# 8But.net
KiCad netlist of a schematic drawn in EAGLE
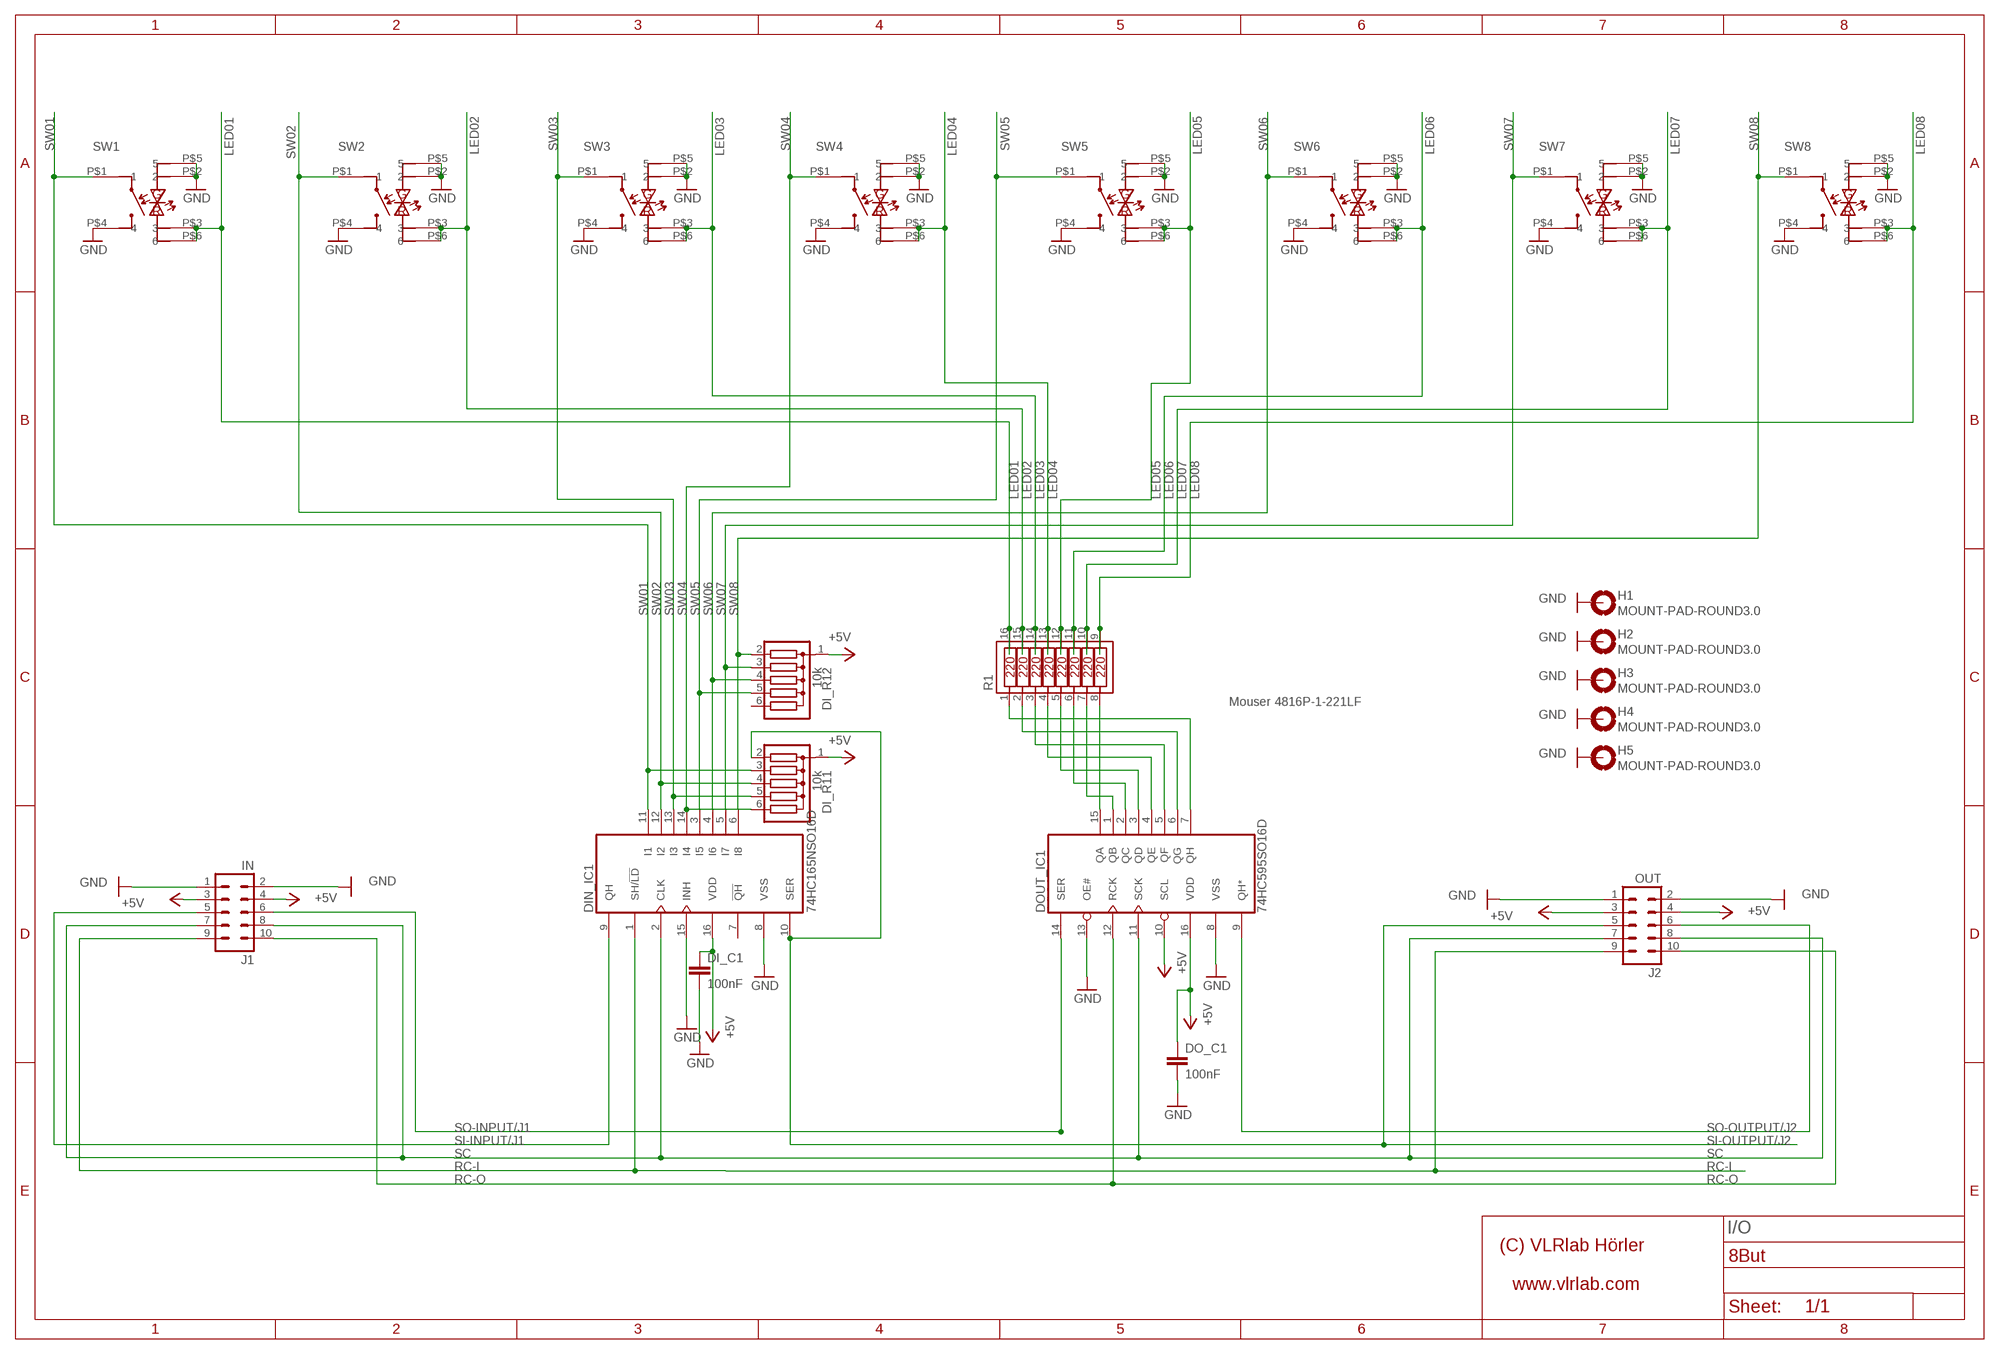
[diagram p0: schematic, sheet 1]

(export (version "E")
  (design (tool "Eeschema 10.0.6"))
  (components
    (comp (ref "DIN_IC1")
      (value "74HC165NSO16D")
      (footprint "eagle-import:SO16D")
      (libsource (lib "eagle-import") (part "74HC165NSO16D"))
    )
    (comp (ref "DI_C1")
      (value "100nF")
      (footprint "eagle-import:C5B3")
      (libsource (lib "eagle-import") (part "C5/3"))
    )
    (comp (ref "DI_R11")
      (value "10k")
      (footprint "eagle-import:SIL6")
      (libsource (lib "eagle-import") (part "4306R"))
    )
    (comp (ref "DI_R12")
      (value "10k")
      (footprint "eagle-import:SIL6")
      (libsource (lib "eagle-import") (part "4306R"))
    )
    (comp (ref "DOUT_IC1")
      (value "74HC595SO16D")
      (footprint "eagle-import:SO16D")
      (libsource (lib "eagle-import") (part "595-541-165-uln2803_74HC595SO16D"))
    )
    (comp (ref "DO_C1")
      (value "100nF")
      (footprint "eagle-import:C5B3")
      (libsource (lib "eagle-import") (part "C5/3"))
    )
    (comp (ref "H1")
      (value "MOUNT-PAD-ROUND3.0")
      (footprint "eagle-import:3,0-PAD")
      (libsource (lib "eagle-import") (part "MOUNT-PAD-ROUND3.0"))
    )
    (comp (ref "H2")
      (value "MOUNT-PAD-ROUND3.0")
      (footprint "eagle-import:3,0-PAD")
      (libsource (lib "eagle-import") (part "MOUNT-PAD-ROUND3.0"))
    )
    (comp (ref "H3")
      (value "MOUNT-PAD-ROUND3.0")
      (footprint "eagle-import:3,0-PAD")
      (libsource (lib "eagle-import") (part "MOUNT-PAD-ROUND3.0"))
    )
    (comp (ref "H4")
      (value "MOUNT-PAD-ROUND3.0")
      (footprint "eagle-import:3,0-PAD")
      (libsource (lib "eagle-import") (part "MOUNT-PAD-ROUND3.0"))
    )
    (comp (ref "H5")
      (value "MOUNT-PAD-ROUND3.0")
      (footprint "eagle-import:3,0-PAD")
      (libsource (lib "eagle-import") (part "MOUNT-PAD-ROUND3.0"))
    )
    (comp (ref "J1")
      (value "IN")
      (footprint "eagle-import:ML10")
      (libsource (lib "eagle-import") (part "ML10"))
    )
    (comp (ref "J2")
      (value "OUT")
      (footprint "eagle-import:ML10")
      (libsource (lib "eagle-import") (part "ML10"))
    )
    (comp (ref "R1")
      (value "4816P-1SOIC16W")
      (footprint "eagle-import:SOIC16W")
      (libsource (lib "eagle-import") (part "4816P-1SOIC16W"))
    )
    (comp (ref "SW1")
      (value "COMB_G3+G5")
      (footprint "eagle-import:COMB_G3+G5")
      (libsource (lib "eagle-import") (part "COMB_G3+G5"))
    )
    (comp (ref "SW2")
      (value "COMB_G3+G5")
      (footprint "eagle-import:COMB_G3+G5")
      (libsource (lib "eagle-import") (part "COMB_G3+G5"))
    )
    (comp (ref "SW3")
      (value "COMB_G3+G5")
      (footprint "eagle-import:COMB_G3+G5")
      (libsource (lib "eagle-import") (part "COMB_G3+G5"))
    )
    (comp (ref "SW4")
      (value "COMB_G3+G5")
      (footprint "eagle-import:COMB_G3+G5")
      (libsource (lib "eagle-import") (part "COMB_G3+G5"))
    )
    (comp (ref "SW5")
      (value "COMB_G3+G5")
      (footprint "eagle-import:COMB_G3+G5")
      (libsource (lib "eagle-import") (part "COMB_G3+G5"))
    )
    (comp (ref "SW6")
      (value "COMB_G3+G5")
      (footprint "eagle-import:COMB_G3+G5")
      (libsource (lib "eagle-import") (part "COMB_G3+G5"))
    )
    (comp (ref "SW7")
      (value "COMB_G3+G5")
      (footprint "eagle-import:COMB_G3+G5")
      (libsource (lib "eagle-import") (part "COMB_G3+G5"))
    )
    (comp (ref "SW8")
      (value "COMB_G3+G5")
      (footprint "eagle-import:COMB_G3+G5")
      (libsource (lib "eagle-import") (part "COMB_G3+G5"))
    )
  )
  (nets
    (net (code "1") (name "+5V") (class "Default")
      (node (ref "DIN_IC1") (pin "16") (pinfunction "VDD_16") (pintype "power_in"))
      (node (ref "DI_C1") (pin "1") (pinfunction "1_1") (pintype "passive"))
      (node (ref "DI_R11") (pin "1") (pinfunction "1_1") (pintype "passive"))
      (node (ref "DI_R12") (pin "1") (pinfunction "1_1") (pintype "passive"))
      (node (ref "DOUT_IC1") (pin "10") (pinfunction "SCL_10") (pintype "input"))
      (node (ref "DOUT_IC1") (pin "16") (pinfunction "VDD_16") (pintype "power_in"))
      (node (ref "DO_C1") (pin "1") (pinfunction "1_1") (pintype "passive"))
      (node (ref "J1") (pin "3") (pinfunction "3_3") (pintype "passive"))
      (node (ref "J1") (pin "4") (pinfunction "4_4") (pintype "passive"))
      (node (ref "J2") (pin "3") (pinfunction "3_3") (pintype "passive"))
      (node (ref "J2") (pin "4") (pinfunction "4_4") (pintype "passive"))
    )
    (net (code "2") (name "/LED01") (class "Default")
      (node (ref "R1") (pin "16") (pinfunction "P$16_16") (pintype "passive"))
      (node (ref "SW1") (pin "P$3") (pinfunction "3_P$3") (pintype "bidirectional"))
      (node (ref "SW1") (pin "P$6") (pinfunction "6_P$6") (pintype "bidirectional"))
    )
    (net (code "3") (name "/LED02") (class "Default")
      (node (ref "R1") (pin "15") (pinfunction "P$15_15") (pintype "passive"))
      (node (ref "SW2") (pin "P$3") (pinfunction "3_P$3") (pintype "bidirectional"))
      (node (ref "SW2") (pin "P$6") (pinfunction "6_P$6") (pintype "bidirectional"))
    )
    (net (code "4") (name "/LED03") (class "Default")
      (node (ref "R1") (pin "14") (pinfunction "P$14_14") (pintype "passive"))
      (node (ref "SW3") (pin "P$3") (pinfunction "3_P$3") (pintype "bidirectional"))
      (node (ref "SW3") (pin "P$6") (pinfunction "6_P$6") (pintype "bidirectional"))
    )
    (net (code "5") (name "/LED04") (class "Default")
      (node (ref "R1") (pin "13") (pinfunction "P$13_13") (pintype "passive"))
      (node (ref "SW4") (pin "P$3") (pinfunction "3_P$3") (pintype "bidirectional"))
      (node (ref "SW4") (pin "P$6") (pinfunction "6_P$6") (pintype "bidirectional"))
    )
    (net (code "6") (name "/LED05") (class "Default")
      (node (ref "R1") (pin "12") (pinfunction "P$12_12") (pintype "passive"))
      (node (ref "SW5") (pin "P$3") (pinfunction "3_P$3") (pintype "bidirectional"))
      (node (ref "SW5") (pin "P$6") (pinfunction "6_P$6") (pintype "bidirectional"))
    )
    (net (code "7") (name "/LED06") (class "Default")
      (node (ref "R1") (pin "11") (pinfunction "P$11_11") (pintype "passive"))
      (node (ref "SW6") (pin "P$3") (pinfunction "3_P$3") (pintype "bidirectional"))
      (node (ref "SW6") (pin "P$6") (pinfunction "6_P$6") (pintype "bidirectional"))
    )
    (net (code "8") (name "/LED07") (class "Default")
      (node (ref "R1") (pin "10") (pinfunction "P$10_10") (pintype "passive"))
      (node (ref "SW7") (pin "P$3") (pinfunction "3_P$3") (pintype "bidirectional"))
      (node (ref "SW7") (pin "P$6") (pinfunction "6_P$6") (pintype "bidirectional"))
    )
    (net (code "9") (name "/LED08") (class "Default")
      (node (ref "R1") (pin "9") (pinfunction "P$9_9") (pintype "passive"))
      (node (ref "SW8") (pin "P$3") (pinfunction "3_P$3") (pintype "bidirectional"))
      (node (ref "SW8") (pin "P$6") (pinfunction "6_P$6") (pintype "bidirectional"))
    )
    (net (code "10") (name "/RC-I") (class "Default")
      (node (ref "DIN_IC1") (pin "1") (pinfunction "SH/~{LD}_1") (pintype "input"))
      (node (ref "J1") (pin "9") (pinfunction "9_9") (pintype "passive"))
      (node (ref "J2") (pin "9") (pinfunction "9_9") (pintype "passive"))
    )
    (net (code "11") (name "/RC-O") (class "Default")
      (node (ref "DOUT_IC1") (pin "12") (pinfunction "RCK_12") (pintype "input"))
      (node (ref "J1") (pin "10") (pinfunction "10_10") (pintype "passive"))
      (node (ref "J2") (pin "10") (pinfunction "10_10") (pintype "passive"))
    )
    (net (code "12") (name "/SC") (class "Default")
      (node (ref "DIN_IC1") (pin "2") (pinfunction "CLK_2") (pintype "input"))
      (node (ref "DOUT_IC1") (pin "11") (pinfunction "SCK_11") (pintype "input"))
      (node (ref "J1") (pin "7") (pinfunction "7_7") (pintype "passive"))
      (node (ref "J1") (pin "8") (pinfunction "8_8") (pintype "passive"))
      (node (ref "J2") (pin "7") (pinfunction "7_7") (pintype "passive"))
      (node (ref "J2") (pin "8") (pinfunction "8_8") (pintype "passive"))
    )
    (net (code "13") (name "/SI-INPUT{slash}J1") (class "Default")
      (node (ref "DIN_IC1") (pin "9") (pinfunction "QH_9") (pintype "output"))
      (node (ref "J1") (pin "5") (pinfunction "5_5") (pintype "passive"))
    )
    (net (code "14") (name "/SI-OUTPUT{slash}J2") (class "Default")
      (node (ref "DIN_IC1") (pin "10") (pinfunction "SER_10") (pintype "input"))
      (node (ref "DI_R11") (pin "2") (pinfunction "2_2") (pintype "passive"))
      (node (ref "J2") (pin "5") (pinfunction "5_5") (pintype "passive"))
    )
    (net (code "15") (name "/SO-INPUT{slash}J1") (class "Default")
      (node (ref "DOUT_IC1") (pin "14") (pinfunction "SER_14") (pintype "input"))
      (node (ref "J1") (pin "6") (pinfunction "6_6") (pintype "passive"))
    )
    (net (code "16") (name "/SO-OUTPUT{slash}J2") (class "Default")
      (node (ref "DOUT_IC1") (pin "9") (pinfunction "QH*_9") (pintype "tri_state"))
      (node (ref "J2") (pin "6") (pinfunction "6_6") (pintype "passive"))
    )
    (net (code "17") (name "/SW01") (class "Default")
      (node (ref "DIN_IC1") (pin "11") (pinfunction "I1_11") (pintype "input"))
      (node (ref "DI_R11") (pin "3") (pinfunction "3_3") (pintype "passive"))
      (node (ref "SW1") (pin "P$1") (pinfunction "1_P$1") (pintype "bidirectional"))
    )
    (net (code "18") (name "/SW02") (class "Default")
      (node (ref "DIN_IC1") (pin "12") (pinfunction "I2_12") (pintype "input"))
      (node (ref "DI_R11") (pin "4") (pinfunction "4_4") (pintype "passive"))
      (node (ref "SW2") (pin "P$1") (pinfunction "1_P$1") (pintype "bidirectional"))
    )
    (net (code "19") (name "/SW03") (class "Default")
      (node (ref "DIN_IC1") (pin "13") (pinfunction "I3_13") (pintype "input"))
      (node (ref "DI_R11") (pin "5") (pinfunction "5_5") (pintype "passive"))
      (node (ref "SW3") (pin "P$1") (pinfunction "1_P$1") (pintype "bidirectional"))
    )
    (net (code "20") (name "/SW04") (class "Default")
      (node (ref "DIN_IC1") (pin "14") (pinfunction "I4_14") (pintype "input"))
      (node (ref "DI_R11") (pin "6") (pinfunction "6_6") (pintype "passive"))
      (node (ref "SW4") (pin "P$1") (pinfunction "1_P$1") (pintype "bidirectional"))
    )
    (net (code "21") (name "/SW05") (class "Default")
      (node (ref "DIN_IC1") (pin "3") (pinfunction "I5_3") (pintype "input"))
      (node (ref "DI_R12") (pin "5") (pinfunction "5_5") (pintype "passive"))
      (node (ref "SW5") (pin "P$1") (pinfunction "1_P$1") (pintype "bidirectional"))
    )
    (net (code "22") (name "/SW06") (class "Default")
      (node (ref "DIN_IC1") (pin "4") (pinfunction "I6_4") (pintype "input"))
      (node (ref "DI_R12") (pin "4") (pinfunction "4_4") (pintype "passive"))
      (node (ref "SW6") (pin "P$1") (pinfunction "1_P$1") (pintype "bidirectional"))
    )
    (net (code "23") (name "/SW07") (class "Default")
      (node (ref "DIN_IC1") (pin "5") (pinfunction "I7_5") (pintype "input"))
      (node (ref "DI_R12") (pin "3") (pinfunction "3_3") (pintype "passive"))
      (node (ref "SW7") (pin "P$1") (pinfunction "1_P$1") (pintype "bidirectional"))
    )
    (net (code "24") (name "/SW08") (class "Default")
      (node (ref "DIN_IC1") (pin "6") (pinfunction "I8_6") (pintype "input"))
      (node (ref "DI_R12") (pin "2") (pinfunction "2_2") (pintype "passive"))
      (node (ref "SW8") (pin "P$1") (pinfunction "1_P$1") (pintype "bidirectional"))
    )
    (net (code "25") (name "GND") (class "Default")
      (node (ref "DIN_IC1") (pin "15") (pinfunction "INH_15") (pintype "input"))
      (node (ref "DIN_IC1") (pin "8") (pinfunction "VSS_8") (pintype "power_in"))
      (node (ref "DI_C1") (pin "2") (pinfunction "2_2") (pintype "passive"))
      (node (ref "DOUT_IC1") (pin "13") (pinfunction "OE#_13") (pintype "input"))
      (node (ref "DOUT_IC1") (pin "8") (pinfunction "VSS_8") (pintype "power_in"))
      (node (ref "DO_C1") (pin "2") (pinfunction "2_2") (pintype "passive"))
      (node (ref "H1") (pin "B3,0") (pinfunction "MOUNT_B3,0") (pintype "passive"))
      (node (ref "H2") (pin "B3,0") (pinfunction "MOUNT_B3,0") (pintype "passive"))
      (node (ref "H3") (pin "B3,0") (pinfunction "MOUNT_B3,0") (pintype "passive"))
      (node (ref "H4") (pin "B3,0") (pinfunction "MOUNT_B3,0") (pintype "passive"))
      (node (ref "H5") (pin "B3,0") (pinfunction "MOUNT_B3,0") (pintype "passive"))
      (node (ref "J1") (pin "1") (pinfunction "1_1") (pintype "passive"))
      (node (ref "J1") (pin "2") (pinfunction "2_2") (pintype "passive"))
      (node (ref "J2") (pin "1") (pinfunction "1_1") (pintype "passive"))
      (node (ref "J2") (pin "2") (pinfunction "2_2") (pintype "passive"))
      (node (ref "SW1") (pin "P$2") (pinfunction "2_P$2") (pintype "bidirectional"))
      (node (ref "SW1") (pin "P$4") (pinfunction "4_P$4") (pintype "bidirectional"))
      (node (ref "SW1") (pin "P$5") (pinfunction "5_P$5") (pintype "bidirectional"))
      (node (ref "SW2") (pin "P$2") (pinfunction "2_P$2") (pintype "bidirectional"))
      (node (ref "SW2") (pin "P$4") (pinfunction "4_P$4") (pintype "bidirectional"))
      (node (ref "SW2") (pin "P$5") (pinfunction "5_P$5") (pintype "bidirectional"))
      (node (ref "SW3") (pin "P$2") (pinfunction "2_P$2") (pintype "bidirectional"))
      (node (ref "SW3") (pin "P$4") (pinfunction "4_P$4") (pintype "bidirectional"))
      (node (ref "SW3") (pin "P$5") (pinfunction "5_P$5") (pintype "bidirectional"))
      (node (ref "SW4") (pin "P$2") (pinfunction "2_P$2") (pintype "bidirectional"))
      (node (ref "SW4") (pin "P$4") (pinfunction "4_P$4") (pintype "bidirectional"))
      (node (ref "SW4") (pin "P$5") (pinfunction "5_P$5") (pintype "bidirectional"))
      (node (ref "SW5") (pin "P$2") (pinfunction "2_P$2") (pintype "bidirectional"))
      (node (ref "SW5") (pin "P$4") (pinfunction "4_P$4") (pintype "bidirectional"))
      (node (ref "SW5") (pin "P$5") (pinfunction "5_P$5") (pintype "bidirectional"))
      (node (ref "SW6") (pin "P$2") (pinfunction "2_P$2") (pintype "bidirectional"))
      (node (ref "SW6") (pin "P$4") (pinfunction "4_P$4") (pintype "bidirectional"))
      (node (ref "SW6") (pin "P$5") (pinfunction "5_P$5") (pintype "bidirectional"))
      (node (ref "SW7") (pin "P$2") (pinfunction "2_P$2") (pintype "bidirectional"))
      (node (ref "SW7") (pin "P$4") (pinfunction "4_P$4") (pintype "bidirectional"))
      (node (ref "SW7") (pin "P$5") (pinfunction "5_P$5") (pintype "bidirectional"))
      (node (ref "SW8") (pin "P$2") (pinfunction "2_P$2") (pintype "bidirectional"))
      (node (ref "SW8") (pin "P$4") (pinfunction "4_P$4") (pintype "bidirectional"))
      (node (ref "SW8") (pin "P$5") (pinfunction "5_P$5") (pintype "bidirectional"))
    )
    (net (code "26") (name "Net-(DOUT_IC1-QA)") (class "Default")
      (node (ref "DOUT_IC1") (pin "15") (pinfunction "QA_15") (pintype "tri_state"))
      (node (ref "R1") (pin "8") (pinfunction "P$8_8") (pintype "passive"))
    )
    (net (code "27") (name "Net-(DOUT_IC1-QB)") (class "Default")
      (node (ref "DOUT_IC1") (pin "1") (pinfunction "QB_1") (pintype "tri_state"))
      (node (ref "R1") (pin "7") (pinfunction "P$7_7") (pintype "passive"))
    )
    (net (code "28") (name "Net-(DOUT_IC1-QC)") (class "Default")
      (node (ref "DOUT_IC1") (pin "2") (pinfunction "QC_2") (pintype "tri_state"))
      (node (ref "R1") (pin "6") (pinfunction "P$6_6") (pintype "passive"))
    )
    (net (code "29") (name "Net-(DOUT_IC1-QD)") (class "Default")
      (node (ref "DOUT_IC1") (pin "3") (pinfunction "QD_3") (pintype "tri_state"))
      (node (ref "R1") (pin "5") (pinfunction "P$5_5") (pintype "passive"))
    )
    (net (code "30") (name "Net-(DOUT_IC1-QE)") (class "Default")
      (node (ref "DOUT_IC1") (pin "4") (pinfunction "QE_4") (pintype "tri_state"))
      (node (ref "R1") (pin "4") (pinfunction "P$4_4") (pintype "passive"))
    )
    (net (code "31") (name "Net-(DOUT_IC1-QF)") (class "Default")
      (node (ref "DOUT_IC1") (pin "5") (pinfunction "QF_5") (pintype "tri_state"))
      (node (ref "R1") (pin "3") (pinfunction "P$3_3") (pintype "passive"))
    )
    (net (code "32") (name "Net-(DOUT_IC1-QG)") (class "Default")
      (node (ref "DOUT_IC1") (pin "6") (pinfunction "QG_6") (pintype "tri_state"))
      (node (ref "R1") (pin "2") (pinfunction "P$2_2") (pintype "passive"))
    )
    (net (code "33") (name "Net-(DOUT_IC1-QH)") (class "Default")
      (node (ref "DOUT_IC1") (pin "7") (pinfunction "QH_7") (pintype "tri_state"))
      (node (ref "R1") (pin "1") (pinfunction "P$1_1") (pintype "passive"))
    )
    (net (code "34") (name "unconnected-(DIN_IC1-~{QH}-Pad7)") (class "Default")
      (node (ref "DIN_IC1") (pin "7") (pinfunction "~{QH}_7") (pintype "output"))
    )
    (net (code "35") (name "unconnected-(DI_R12-Pad6)") (class "Default")
      (node (ref "DI_R12") (pin "6") (pinfunction "6_6") (pintype "passive"))
    )
  )
)
